# euxoloti_core_rev2.net
KiCad netlist of a schematic drawn in EAGLE
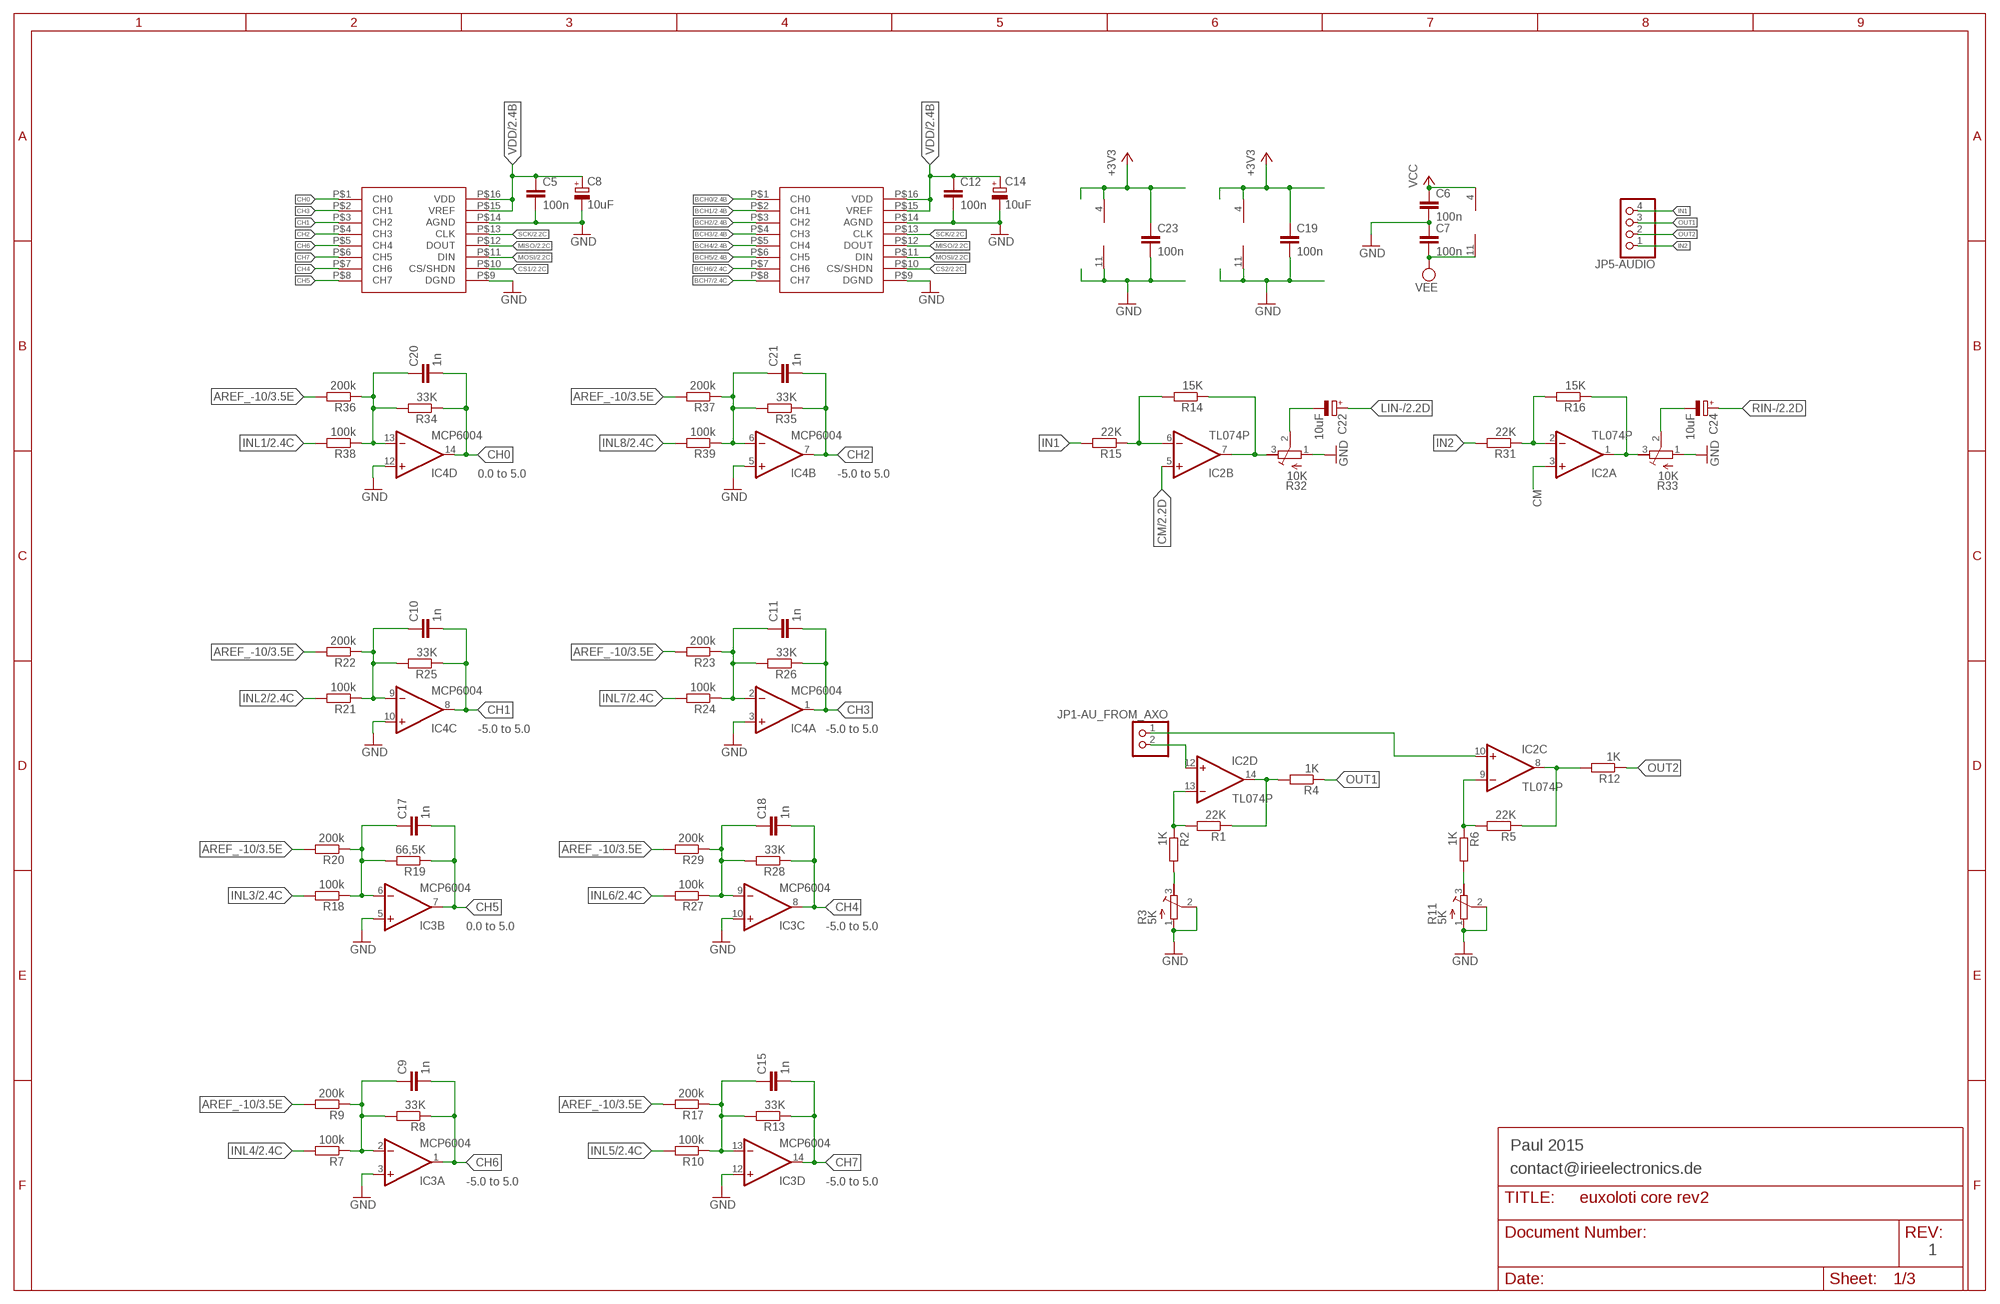
[diagram p0: schematic, sheet 1]
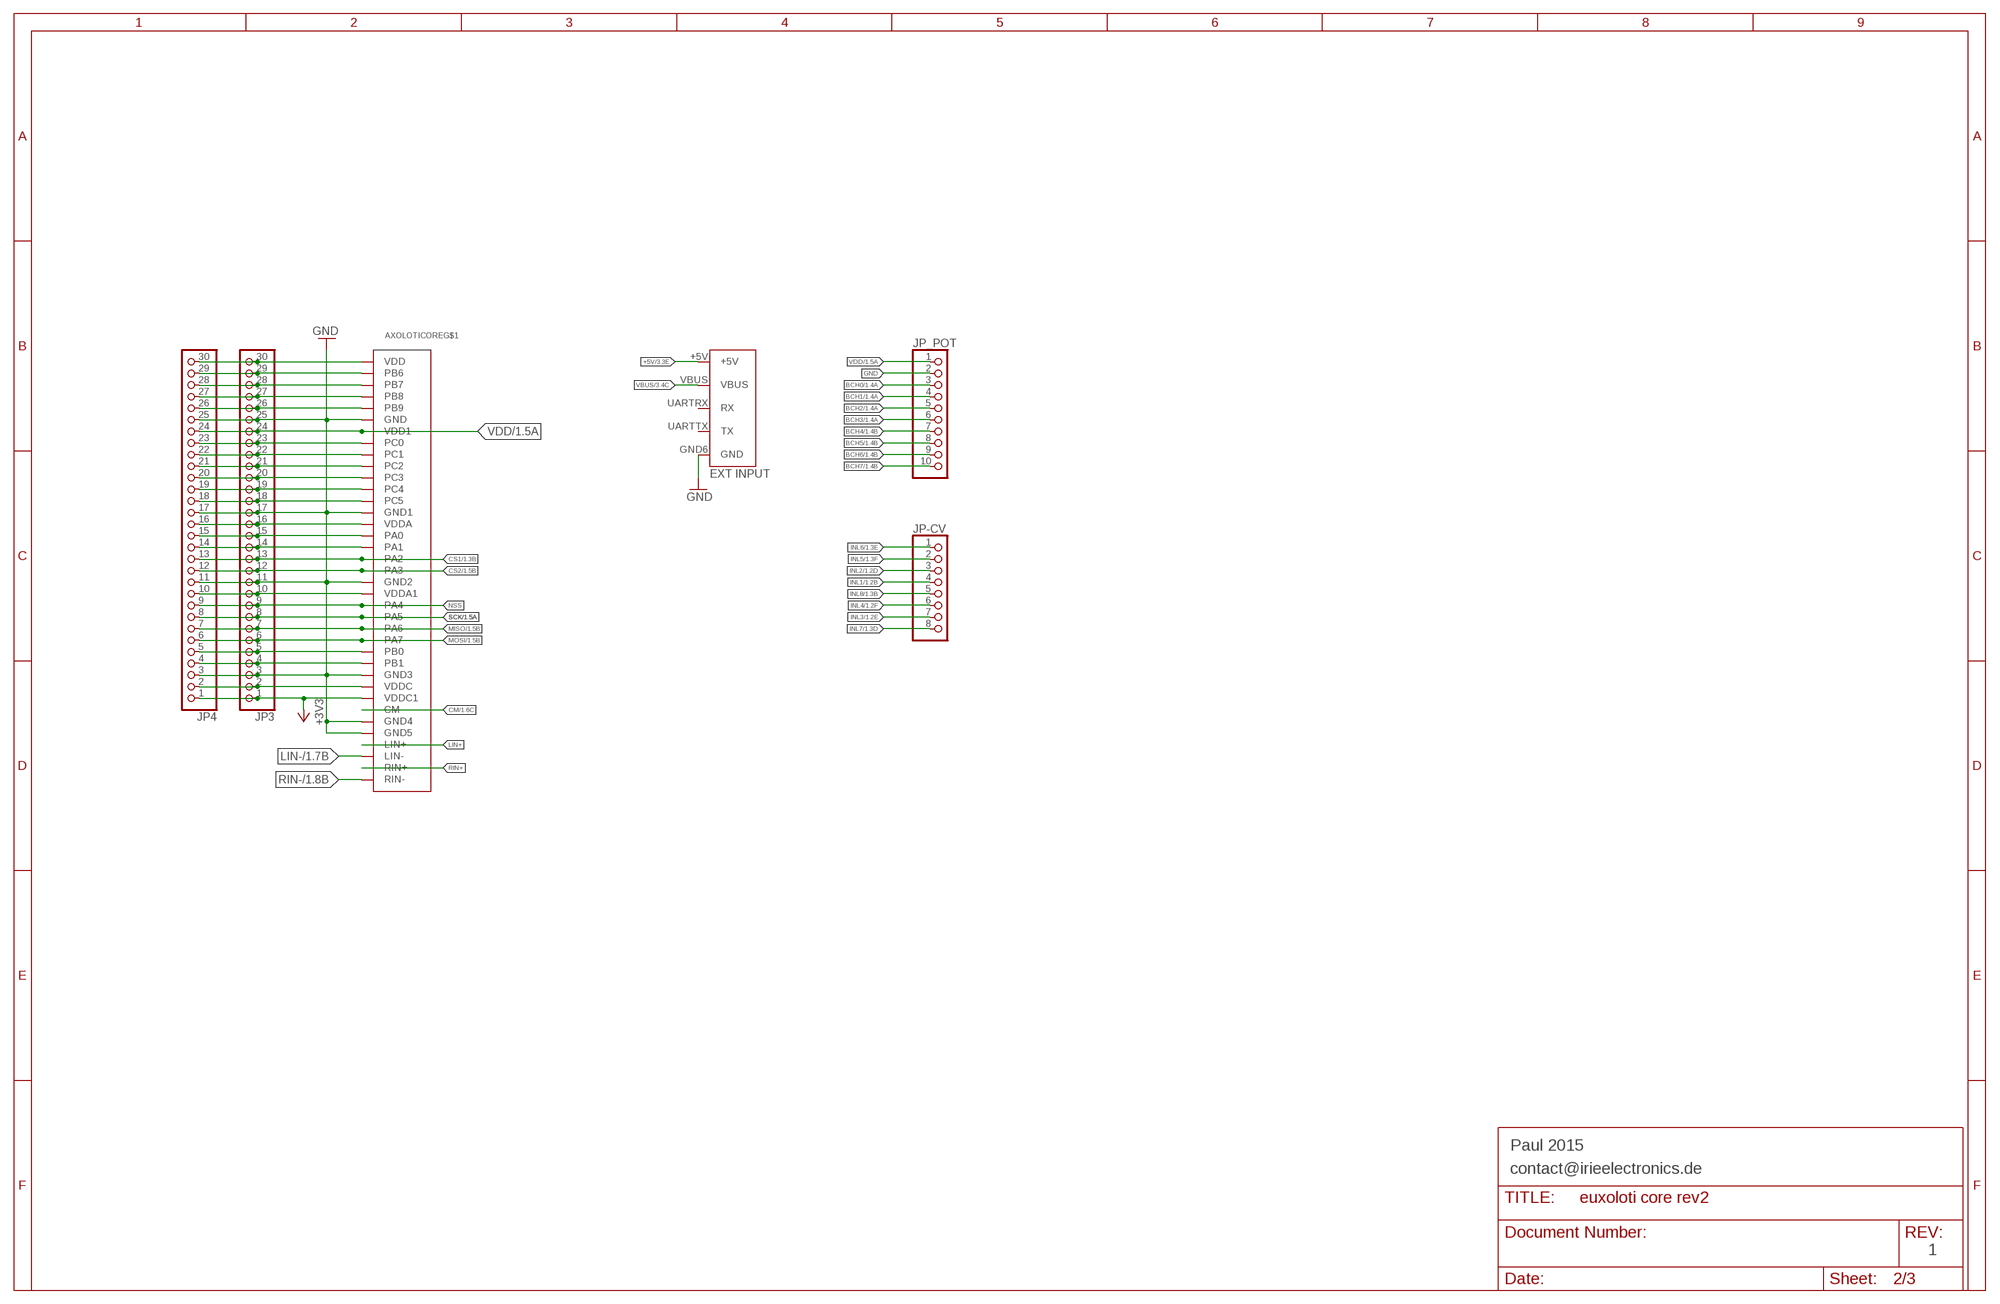
[diagram p1: schematic, sheet 2]
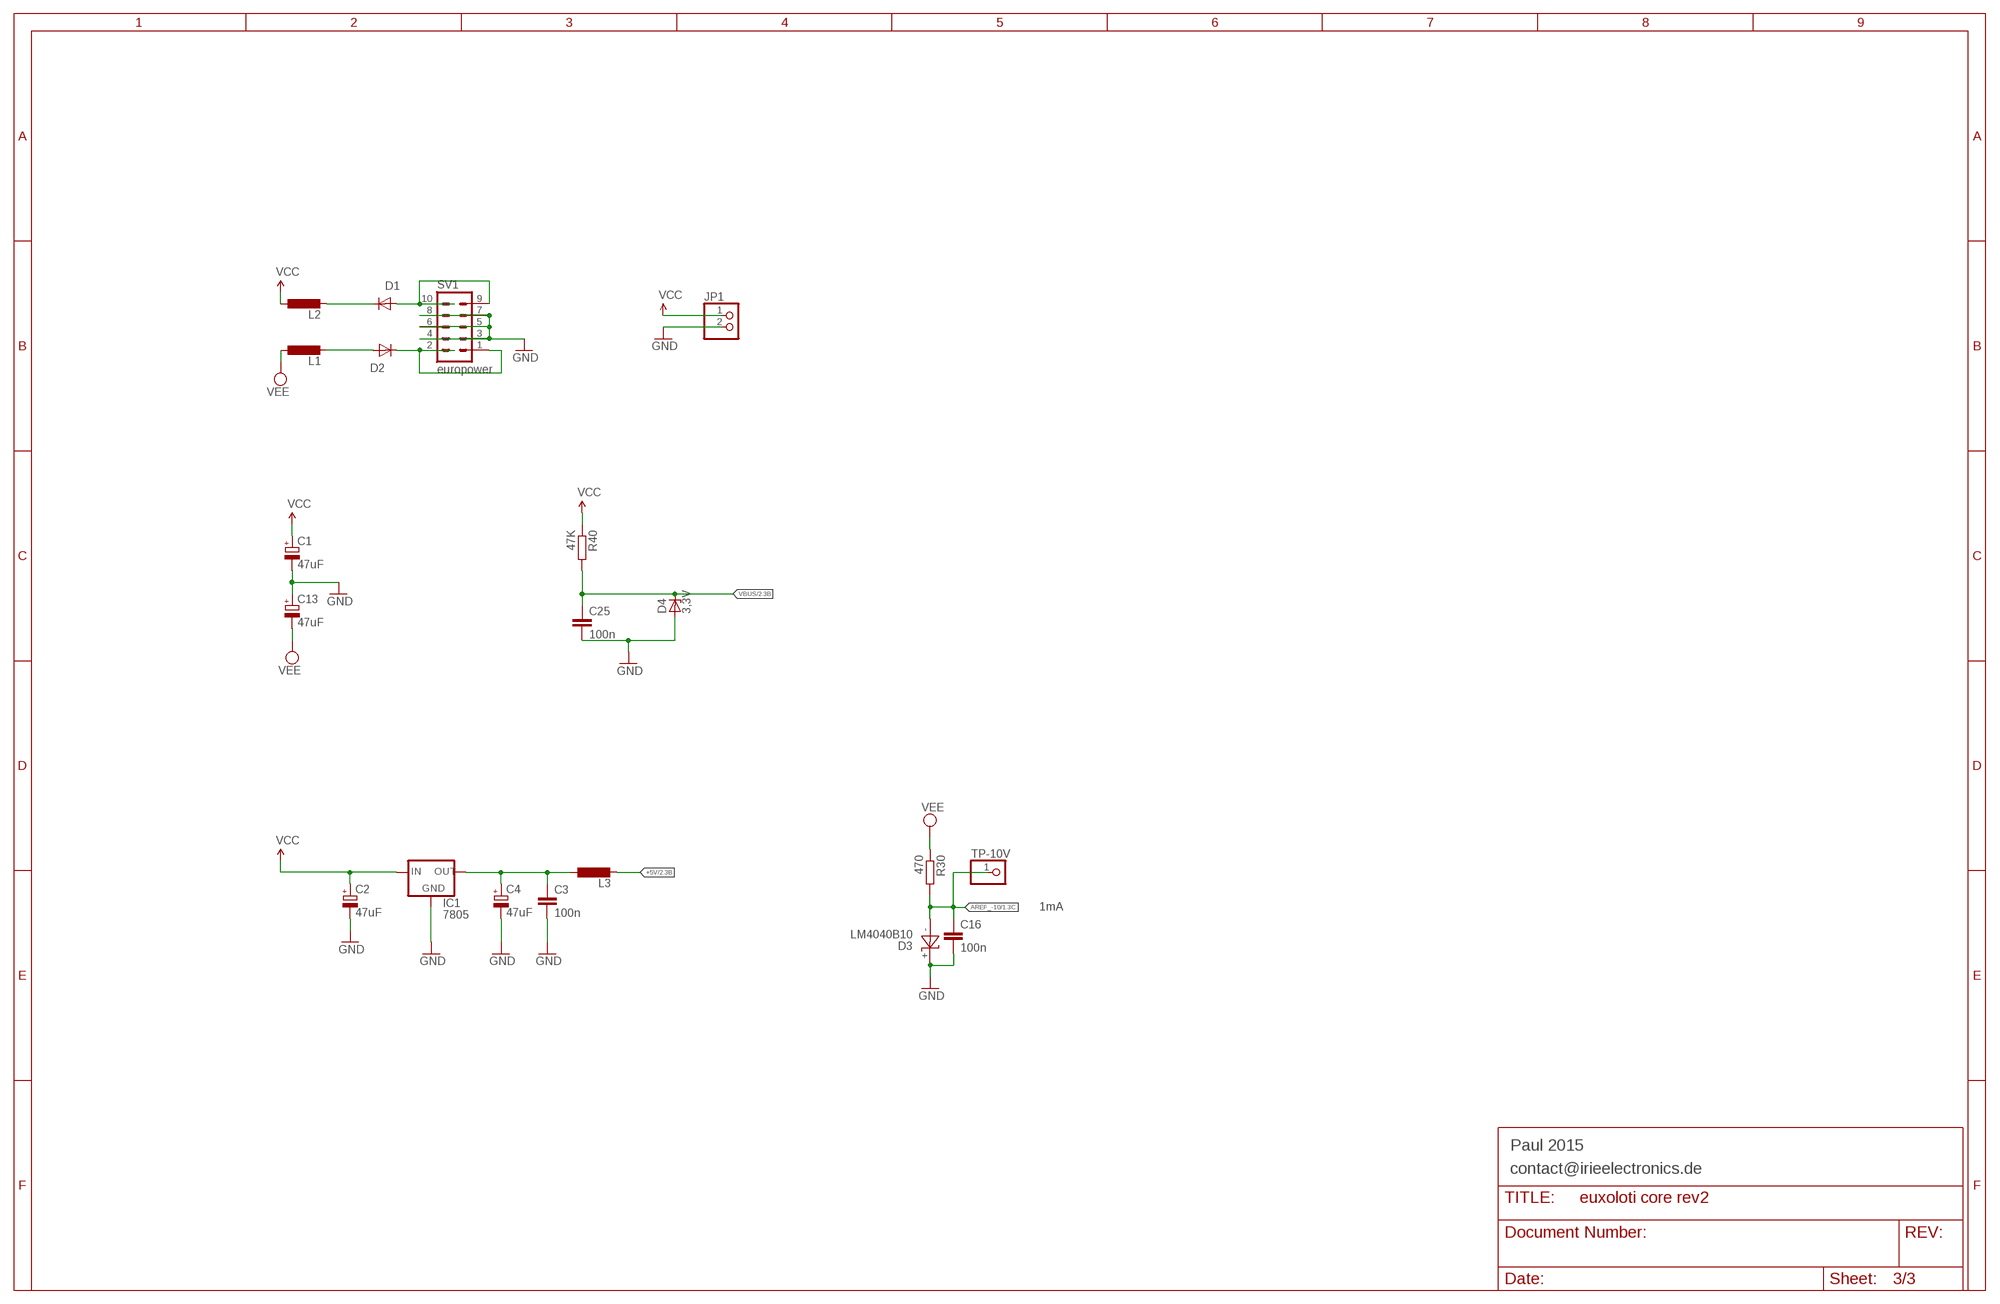
[diagram p2: schematic, sheet 3]

(export (version "E")
  (design (tool "Eeschema 10.0.6"))
  (components
    (comp (ref "C1")
      (value "47uF")
      (footprint "eagle-import:E2-5")
      (libsource (lib "eagle-import") (part "CPOL-EUE2-5"))
    )
    (comp (ref "C2")
      (value "47uF")
      (footprint "eagle-import:E2-5")
      (libsource (lib "eagle-import") (part "CPOL-EUE2-5"))
    )
    (comp (ref "C3")
      (value "100n")
      (footprint "eagle-import:C025-025X050")
      (libsource (lib "eagle-import") (part "C-EU025-025X050"))
    )
    (comp (ref "C4")
      (value "47uF")
      (footprint "eagle-import:E2,5-5")
      (libsource (lib "eagle-import") (part "CPOL-EUE2.5-5"))
    )
    (comp (ref "C13")
      (value "47uF")
      (footprint "eagle-import:E2-5")
      (libsource (lib "eagle-import") (part "CPOL-EUE2-5"))
    )
    (comp (ref "C16")
      (value "100n")
      (footprint "eagle-import:C025-025X050")
      (libsource (lib "eagle-import") (part "C-EU025-025X050"))
    )
    (comp (ref "C25")
      (value "100n")
      (footprint "eagle-import:C025-025X050")
      (libsource (lib "eagle-import") (part "C-EU025-025X050"))
    )
    (comp (ref "D1")
      (value "1N5819HW")
      (footprint "eagle-import:DO35-10")
      (libsource (lib "eagle-import") (part "1N4148DO35-10"))
    )
    (comp (ref "D2")
      (value "1N5819HW")
      (footprint "eagle-import:DO35-10")
      (libsource (lib "eagle-import") (part "1N4148DO35-10"))
    )
    (comp (ref "D3")
      (value "LM4040B10")
      (footprint "eagle-import:TO-92")
      (libsource (lib "eagle-import") (part "LM4040DIP"))
    )
    (comp (ref "D4")
      (value "3,3V")
      (footprint "eagle-import:DO35Z10")
      (libsource (lib "eagle-import") (part "1N821"))
    )
    (comp (ref "IC1")
      (value "7805")
      (footprint "eagle-import:78XXS")
      (libsource (lib "eagle-import") (part "78XXS"))
    )
    (comp (ref "JP1")
      (value "PINHD-1X2")
      (footprint "eagle-import:1X02")
      (libsource (lib "eagle-import") (part "PINHD-1X2"))
    )
    (comp (ref "L1")
      (value "L-EU0207/10")
      (footprint "eagle-import:0207_10")
      (libsource (lib "eagle-import") (part "L-EU0207/10"))
    )
    (comp (ref "L2")
      (value "L-EU0207/10")
      (footprint "eagle-import:0207_10")
      (libsource (lib "eagle-import") (part "L-EU0207/10"))
    )
    (comp (ref "L3")
      (value "L-EU0207/10")
      (footprint "eagle-import:0207_10")
      (libsource (lib "eagle-import") (part "L-EU0207/10"))
    )
    (comp (ref "R30")
      (value "470")
      (footprint "eagle-import:0207_12")
      (libsource (lib "eagle-import") (part "R-EU_0207/12"))
    )
    (comp (ref "R40")
      (value "47K")
      (footprint "eagle-import:0207_7")
      (libsource (lib "eagle-import") (part "R-EU_0207/7"))
    )
    (comp (ref "SV1")
      (value "europower")
      (footprint "eagle-import:EURO_PWR_HEADER_FAT")
      (libsource (lib "eagle-import") (part "EURO_POWER_HEADERFAT_PADS"))
    )
    (comp (ref "TP-10V")
      (value "PINHD-1X1_2.54")
      (footprint "eagle-import:1X01")
      (libsource (lib "eagle-import") (part "PINHD-1X1_2.54"))
    )
    (comp (ref "C5")
      (value "100n")
      (footprint "eagle-import:C025-025X050")
      (libsource (lib "eagle-import") (part "C-EU025-025X050"))
    )
    (comp (ref "C6")
      (value "100n")
      (footprint "eagle-import:C025-025X050")
      (libsource (lib "eagle-import") (part "C-EU025-025X050"))
    )
    (comp (ref "C7")
      (value "100n")
      (footprint "eagle-import:C025-025X050")
      (libsource (lib "eagle-import") (part "C-EU025-025X050"))
    )
    (comp (ref "C8")
      (value "10uF")
      (footprint "eagle-import:E1,8-4")
      (libsource (lib "eagle-import") (part "CPOL-EUE1.8-4"))
    )
    (comp (ref "C9")
      (value "1n")
      (footprint "eagle-import:C050-025X075")
      (libsource (lib "eagle-import") (part "C-EU050-025X075"))
    )
    (comp (ref "C10")
      (value "1n")
      (footprint "eagle-import:C050-025X075")
      (libsource (lib "eagle-import") (part "C-EU050-025X075"))
    )
    (comp (ref "C11")
      (value "1n")
      (footprint "eagle-import:C050-025X075")
      (libsource (lib "eagle-import") (part "C-EU050-025X075"))
    )
    (comp (ref "C12")
      (value "100n")
      (footprint "eagle-import:C025-025X050")
      (libsource (lib "eagle-import") (part "C-EU025-025X050"))
    )
    (comp (ref "C14")
      (value "10uF")
      (footprint "eagle-import:E1,8-4")
      (libsource (lib "eagle-import") (part "CPOL-EUE1.8-4"))
    )
    (comp (ref "C15")
      (value "1n")
      (footprint "eagle-import:C050-025X075")
      (libsource (lib "eagle-import") (part "C-EU050-025X075"))
    )
    (comp (ref "C17")
      (value "1n")
      (footprint "eagle-import:C050-025X075")
      (libsource (lib "eagle-import") (part "C-EU050-025X075"))
    )
    (comp (ref "C18")
      (value "1n")
      (footprint "eagle-import:C050-025X075")
      (libsource (lib "eagle-import") (part "C-EU050-025X075"))
    )
    (comp (ref "C19")
      (value "100n")
      (footprint "eagle-import:C025-025X050")
      (libsource (lib "eagle-import") (part "C-EU025-025X050"))
    )
    (comp (ref "C20")
      (value "1n")
      (footprint "eagle-import:C050-025X075")
      (libsource (lib "eagle-import") (part "C-EU050-025X075"))
    )
    (comp (ref "C21")
      (value "1n")
      (footprint "eagle-import:C050-025X075")
      (libsource (lib "eagle-import") (part "C-EU050-025X075"))
    )
    (comp (ref "C22")
      (value "10uF")
      (footprint "eagle-import:E1,8-4")
      (libsource (lib "eagle-import") (part "CPOL-EUE1.8-4"))
    )
    (comp (ref "C23")
      (value "100n")
      (footprint "eagle-import:C025-025X050")
      (libsource (lib "eagle-import") (part "C-EU025-025X050"))
    )
    (comp (ref "C24")
      (value "10uF")
      (footprint "eagle-import:E1,8-4")
      (libsource (lib "eagle-import") (part "CPOL-EUE1.8-4"))
    )
    (comp (ref "IC2")
      (value "TL074P")
      (footprint "eagle-import:DIL14")
      (libsource (lib "eagle-import") (part "TL074P"))
    )
    (comp (ref "IC3")
      (value "MCP6004")
      (footprint "eagle-import:DIL14")
      (libsource (lib "eagle-import") (part "TL074P"))
    )
    (comp (ref "IC4")
      (value "MCP6004")
      (footprint "eagle-import:DIL14")
      (libsource (lib "eagle-import") (part "TL074P"))
    )
    (comp (ref "JP1-AU_FROM_AXO")
      (value "PINHD-1X2/90")
      (footprint "eagle-import:1X02_90")
      (libsource (lib "eagle-import") (part "PINHD-1X2/90"))
    )
    (comp (ref "JP5-AUDIO")
      (value "PINHD-1X4_2.54")
      (footprint "eagle-import:1X04")
      (libsource (lib "eagle-import") (part "PINHD-1X4_2.54"))
    )
    (comp (ref "R1")
      (value "22K")
      (footprint "eagle-import:0207_10")
      (libsource (lib "eagle-import") (part "R-EU_0207/10"))
    )
    (comp (ref "R2")
      (value "1K")
      (footprint "eagle-import:0207_12")
      (libsource (lib "eagle-import") (part "R-EU_0207/12"))
    )
    (comp (ref "R3")
      (value "5K")
      (footprint "eagle-import:RTRIM3296P")
      (libsource (lib "eagle-import") (part "R-TRIMM3296P"))
    )
    (comp (ref "R4")
      (value "1K")
      (footprint "eagle-import:0207_7")
      (libsource (lib "eagle-import") (part "R-EU_0207/7"))
    )
    (comp (ref "R5")
      (value "22K")
      (footprint "eagle-import:0207_7")
      (libsource (lib "eagle-import") (part "R-EU_0207/7"))
    )
    (comp (ref "R6")
      (value "1K")
      (footprint "eagle-import:0207_7")
      (libsource (lib "eagle-import") (part "R-EU_0207/7"))
    )
    (comp (ref "R7")
      (value "100k")
      (footprint "eagle-import:0207_7")
      (libsource (lib "eagle-import") (part "R-EU_0207/7"))
    )
    (comp (ref "R8")
      (value "33K")
      (footprint "eagle-import:0207_7")
      (libsource (lib "eagle-import") (part "R-EU_0207/7"))
    )
    (comp (ref "R9")
      (value "200k")
      (footprint "eagle-import:0207_10")
      (libsource (lib "eagle-import") (part "R-EU_0207/10"))
    )
    (comp (ref "R10")
      (value "100k")
      (footprint "eagle-import:0207_7")
      (libsource (lib "eagle-import") (part "R-EU_0207/7"))
    )
    (comp (ref "R11")
      (value "5K")
      (footprint "eagle-import:RTRIM3296P")
      (libsource (lib "eagle-import") (part "R-TRIMM3296P"))
    )
    (comp (ref "R12")
      (value "1K")
      (footprint "eagle-import:0207_10")
      (libsource (lib "eagle-import") (part "R-EU_0207/10"))
    )
    (comp (ref "R13")
      (value "33K")
      (footprint "eagle-import:0207_7")
      (libsource (lib "eagle-import") (part "R-EU_0207/7"))
    )
    (comp (ref "R14")
      (value "15K")
      (footprint "eagle-import:0207_7")
      (libsource (lib "eagle-import") (part "R-EU_0207/7"))
    )
    (comp (ref "R15")
      (value "22K")
      (footprint "eagle-import:0207_7")
      (libsource (lib "eagle-import") (part "R-EU_0207/7"))
    )
    (comp (ref "R16")
      (value "15K")
      (footprint "eagle-import:0207_7")
      (libsource (lib "eagle-import") (part "R-EU_0207/7"))
    )
    (comp (ref "R17")
      (value "200k")
      (footprint "eagle-import:0207_7")
      (libsource (lib "eagle-import") (part "R-EU_0207/7"))
    )
    (comp (ref "R18")
      (value "100k")
      (footprint "eagle-import:0207_7")
      (libsource (lib "eagle-import") (part "R-EU_0207/7"))
    )
    (comp (ref "R19")
      (value "66,5K")
      (footprint "eagle-import:0207_7")
      (libsource (lib "eagle-import") (part "R-EU_0207/7"))
    )
    (comp (ref "R20")
      (value "200k")
      (footprint "eagle-import:0207_10")
      (libsource (lib "eagle-import") (part "R-EU_0207/10"))
    )
    (comp (ref "R21")
      (value "100k")
      (footprint "eagle-import:0207_7")
      (libsource (lib "eagle-import") (part "R-EU_0207/7"))
    )
    (comp (ref "R22")
      (value "200k")
      (footprint "eagle-import:0207_7")
      (libsource (lib "eagle-import") (part "R-EU_0207/7"))
    )
    (comp (ref "R23")
      (value "200k")
      (footprint "eagle-import:0207_7")
      (libsource (lib "eagle-import") (part "R-EU_0207/7"))
    )
    (comp (ref "R24")
      (value "100k")
      (footprint "eagle-import:0207_10")
      (libsource (lib "eagle-import") (part "R-EU_0207/10"))
    )
    (comp (ref "R25")
      (value "33K")
      (footprint "eagle-import:0207_7")
      (libsource (lib "eagle-import") (part "R-EU_0207/7"))
    )
    (comp (ref "R26")
      (value "33K")
      (footprint "eagle-import:0207_7")
      (libsource (lib "eagle-import") (part "R-EU_0207/7"))
    )
    (comp (ref "R27")
      (value "100k")
      (footprint "eagle-import:0207_7")
      (libsource (lib "eagle-import") (part "R-EU_0207/7"))
    )
    (comp (ref "R28")
      (value "33K")
      (footprint "eagle-import:0207_7")
      (libsource (lib "eagle-import") (part "R-EU_0207/7"))
    )
    (comp (ref "R29")
      (value "200k")
      (footprint "eagle-import:0207_7")
      (libsource (lib "eagle-import") (part "R-EU_0207/7"))
    )
    (comp (ref "R31")
      (value "22K")
      (footprint "eagle-import:0207_7")
      (libsource (lib "eagle-import") (part "R-EU_0207/7"))
    )
    (comp (ref "R32")
      (value "10K")
      (footprint "eagle-import:RTRIM3296P")
      (libsource (lib "eagle-import") (part "R-TRIMM3296P"))
    )
    (comp (ref "R33")
      (value "10K")
      (footprint "eagle-import:RTRIM3296P")
      (libsource (lib "eagle-import") (part "R-TRIMM3296P"))
    )
    (comp (ref "R34")
      (value "33K")
      (footprint "eagle-import:0207_7")
      (libsource (lib "eagle-import") (part "R-EU_0207/7"))
    )
    (comp (ref "R35")
      (value "33K")
      (footprint "eagle-import:0207_7")
      (libsource (lib "eagle-import") (part "R-EU_0207/7"))
    )
    (comp (ref "R36")
      (value "200k")
      (footprint "eagle-import:0207_7")
      (libsource (lib "eagle-import") (part "R-EU_0207/7"))
    )
    (comp (ref "R37")
      (value "200k")
      (footprint "eagle-import:0207_7")
      (libsource (lib "eagle-import") (part "R-EU_0207/7"))
    )
    (comp (ref "R38")
      (value "100k")
      (footprint "eagle-import:0207_7")
      (libsource (lib "eagle-import") (part "R-EU_0207/7"))
    )
    (comp (ref "R39")
      (value "100k")
      (footprint "eagle-import:0207_7")
      (libsource (lib "eagle-import") (part "R-EU_0207/7"))
    )
    (comp (ref "U$4")
      (value "MCP3208_DIP")
      (footprint "eagle-import:MCP2308")
      (libsource (lib "eagle-import") (part "MCP3208_DIP"))
    )
    (comp (ref "U$5")
      (value "MCP3208_DIP")
      (footprint "eagle-import:MCP2308")
      (libsource (lib "eagle-import") (part "MCP3208_DIP"))
    )
    (comp (ref "AXOLOTICORE")
      (value "AXOLOTI-CORE")
      (footprint "eagle-import:AXOLOTI-CORE")
      (libsource (lib "eagle-import") (part "AXOLOTI-CORE"))
    )
    (comp (ref "JP-CV")
      (value "PINHD-1X8_2.54")
      (footprint "eagle-import:1X08")
      (libsource (lib "eagle-import") (part "PINHD-1X8_2.54"))
    )
    (comp (ref "JP3")
      (value "PINHD-1X30")
      (footprint "eagle-import:1X30")
      (libsource (lib "eagle-import") (part "PINHD-1X30"))
    )
    (comp (ref "JP4")
      (value "PINHD-1X30")
      (footprint "eagle-import:1X30")
      (libsource (lib "eagle-import") (part "PINHD-1X30"))
    )
    (comp (ref "JP_POT")
      (value "PINHD-1X10")
      (footprint "eagle-import:1X10")
      (libsource (lib "eagle-import") (part "PINHD-1X10"))
    )
  )
  (nets
    (net (code "1") (name "+3V3") (class "Default")
      (node (ref "AXOLOTICORE") (pin "VDDC1") (pinfunction "VDDC1_VDDC1") (pintype "bidirectional"))
      (node (ref "C19") (pin "1") (pinfunction "1_1") (pintype "passive"))
      (node (ref "C23") (pin "1") (pinfunction "1_1") (pintype "passive"))
      (node (ref "IC3") (pin "4") (pinfunction "V+_4") (pintype "power_in"))
      (node (ref "IC4") (pin "4") (pinfunction "V+_4") (pintype "power_in"))
      (node (ref "JP3") (pin "1") (pinfunction "1_1") (pintype "passive"))
      (node (ref "JP4") (pin "1") (pinfunction "1_1") (pintype "passive"))
    )
    (net (code "2") (name "+5V") (class "Default")
      (node (ref "AXOLOTICORE") (pin "+5V") (pinfunction "+5V_+5V") (pintype "bidirectional"))
      (node (ref "L3") (pin "2") (pinfunction "2_2") (pintype "passive"))
    )
    (net (code "3") (name "AREF_-10") (class "Default")
      (node (ref "C16") (pin "1") (pinfunction "1_1") (pintype "passive"))
      (node (ref "D3") (pin "-") (pinfunction "-_-") (pintype "output"))
      (node (ref "R17") (pin "2") (pinfunction "2_2") (pintype "passive"))
      (node (ref "R20") (pin "2") (pinfunction "2_2") (pintype "passive"))
      (node (ref "R22") (pin "2") (pinfunction "2_2") (pintype "passive"))
      (node (ref "R23") (pin "2") (pinfunction "2_2") (pintype "passive"))
      (node (ref "R29") (pin "2") (pinfunction "2_2") (pintype "passive"))
      (node (ref "R30") (pin "2") (pinfunction "2_2") (pintype "passive"))
      (node (ref "R36") (pin "2") (pinfunction "2_2") (pintype "passive"))
      (node (ref "R37") (pin "2") (pinfunction "2_2") (pintype "passive"))
      (node (ref "R9") (pin "2") (pinfunction "2_2") (pintype "passive"))
      (node (ref "TP-10V") (pin "1") (pinfunction "1_1") (pintype "passive"))
    )
    (net (code "4") (name "BCH0") (class "Default")
      (node (ref "JP_POT") (pin "3") (pinfunction "3_3") (pintype "passive"))
      (node (ref "U$5") (pin "P$1") (pinfunction "CH0_P$1") (pintype "bidirectional"))
    )
    (net (code "5") (name "BCH1") (class "Default")
      (node (ref "JP_POT") (pin "4") (pinfunction "4_4") (pintype "passive"))
      (node (ref "U$5") (pin "P$2") (pinfunction "CH1_P$2") (pintype "bidirectional"))
    )
    (net (code "6") (name "BCH2") (class "Default")
      (node (ref "JP_POT") (pin "5") (pinfunction "5_5") (pintype "passive"))
      (node (ref "U$5") (pin "P$3") (pinfunction "CH2_P$3") (pintype "bidirectional"))
    )
    (net (code "7") (name "BCH3") (class "Default")
      (node (ref "JP_POT") (pin "6") (pinfunction "6_6") (pintype "passive"))
      (node (ref "U$5") (pin "P$4") (pinfunction "CH3_P$4") (pintype "bidirectional"))
    )
    (net (code "8") (name "BCH4") (class "Default")
      (node (ref "JP_POT") (pin "7") (pinfunction "7_7") (pintype "passive"))
      (node (ref "U$5") (pin "P$5") (pinfunction "CH4_P$5") (pintype "bidirectional"))
    )
    (net (code "9") (name "BCH5") (class "Default")
      (node (ref "JP_POT") (pin "8") (pinfunction "8_8") (pintype "passive"))
      (node (ref "U$5") (pin "P$6") (pinfunction "CH5_P$6") (pintype "bidirectional"))
    )
    (net (code "10") (name "BCH6") (class "Default")
      (node (ref "JP_POT") (pin "9") (pinfunction "9_9") (pintype "passive"))
      (node (ref "U$5") (pin "P$7") (pinfunction "CH6_P$7") (pintype "bidirectional"))
    )
    (net (code "11") (name "BCH7") (class "Default")
      (node (ref "JP_POT") (pin "10") (pinfunction "10_10") (pintype "passive"))
      (node (ref "U$5") (pin "P$8") (pinfunction "CH7_P$8") (pintype "bidirectional"))
    )
    (net (code "12") (name "CH0") (class "Default")
      (node (ref "C20") (pin "2") (pinfunction "2_2") (pintype "passive"))
      (node (ref "IC4") (pin "14") (pinfunction "OUT_14") (pintype "output"))
      (node (ref "R34") (pin "1") (pinfunction "1_1") (pintype "passive"))
      (node (ref "U$4") (pin "P$1") (pinfunction "CH0_P$1") (pintype "bidirectional"))
    )
    (net (code "13") (name "CH1") (class "Default")
      (node (ref "C10") (pin "2") (pinfunction "2_2") (pintype "passive"))
      (node (ref "IC4") (pin "8") (pinfunction "OUT_8") (pintype "output"))
      (node (ref "R25") (pin "1") (pinfunction "1_1") (pintype "passive"))
      (node (ref "U$4") (pin "P$3") (pinfunction "CH2_P$3") (pintype "bidirectional"))
    )
    (net (code "14") (name "CH2") (class "Default")
      (node (ref "C21") (pin "2") (pinfunction "2_2") (pintype "passive"))
      (node (ref "IC4") (pin "7") (pinfunction "OUT_7") (pintype "output"))
      (node (ref "R35") (pin "1") (pinfunction "1_1") (pintype "passive"))
      (node (ref "U$4") (pin "P$4") (pinfunction "CH3_P$4") (pintype "bidirectional"))
    )
    (net (code "15") (name "CH3") (class "Default")
      (node (ref "C11") (pin "2") (pinfunction "2_2") (pintype "passive"))
      (node (ref "IC4") (pin "1") (pinfunction "OUT_1") (pintype "output"))
      (node (ref "R26") (pin "1") (pinfunction "1_1") (pintype "passive"))
      (node (ref "U$4") (pin "P$2") (pinfunction "CH1_P$2") (pintype "bidirectional"))
    )
    (net (code "16") (name "CH4") (class "Default")
      (node (ref "C18") (pin "2") (pinfunction "2_2") (pintype "passive"))
      (node (ref "IC3") (pin "8") (pinfunction "OUT_8") (pintype "output"))
      (node (ref "R28") (pin "1") (pinfunction "1_1") (pintype "passive"))
      (node (ref "U$4") (pin "P$7") (pinfunction "CH6_P$7") (pintype "bidirectional"))
    )
    (net (code "17") (name "CH5") (class "Default")
      (node (ref "C17") (pin "2") (pinfunction "2_2") (pintype "passive"))
      (node (ref "IC3") (pin "7") (pinfunction "OUT_7") (pintype "output"))
      (node (ref "R19") (pin "1") (pinfunction "1_1") (pintype "passive"))
      (node (ref "U$4") (pin "P$8") (pinfunction "CH7_P$8") (pintype "bidirectional"))
    )
    (net (code "18") (name "CH6") (class "Default")
      (node (ref "C9") (pin "2") (pinfunction "2_2") (pintype "passive"))
      (node (ref "IC3") (pin "1") (pinfunction "OUT_1") (pintype "output"))
      (node (ref "R8") (pin "1") (pinfunction "1_1") (pintype "passive"))
      (node (ref "U$4") (pin "P$5") (pinfunction "CH4_P$5") (pintype "bidirectional"))
    )
    (net (code "19") (name "CH7") (class "Default")
      (node (ref "C15") (pin "2") (pinfunction "2_2") (pintype "passive"))
      (node (ref "IC3") (pin "14") (pinfunction "OUT_14") (pintype "output"))
      (node (ref "R13") (pin "1") (pinfunction "1_1") (pintype "passive"))
      (node (ref "U$4") (pin "P$6") (pinfunction "CH5_P$6") (pintype "bidirectional"))
    )
    (net (code "20") (name "CM") (class "Default")
      (node (ref "AXOLOTICORE") (pin "CM") (pinfunction "CM_CM") (pintype "bidirectional"))
      (node (ref "IC2") (pin "3") (pinfunction "+IN_3") (pintype "input"))
      (node (ref "IC2") (pin "5") (pinfunction "+IN_5") (pintype "input"))
    )
    (net (code "21") (name "CS1") (class "Default")
      (node (ref "AXOLOTICORE") (pin "PA2") (pinfunction "PA2_PA2") (pintype "bidirectional"))
      (node (ref "JP3") (pin "13") (pinfunction "13_13") (pintype "passive"))
      (node (ref "JP4") (pin "13") (pinfunction "13_13") (pintype "passive"))
      (node (ref "U$4") (pin "P$10") (pinfunction "CS/SHDN_P$10") (pintype "bidirectional"))
    )
    (net (code "22") (name "CS2") (class "Default")
      (node (ref "AXOLOTICORE") (pin "PA3") (pinfunction "PA3_PA3") (pintype "bidirectional"))
      (node (ref "JP3") (pin "12") (pinfunction "12_12") (pintype "passive"))
      (node (ref "JP4") (pin "12") (pinfunction "12_12") (pintype "passive"))
      (node (ref "U$5") (pin "P$10") (pinfunction "CS/SHDN_P$10") (pintype "bidirectional"))
    )
    (net (code "23") (name "GND") (class "Default")
      (node (ref "AXOLOTICORE") (pin "GND") (pinfunction "GND_GND") (pintype "bidirectional"))
      (node (ref "AXOLOTICORE") (pin "GND1") (pinfunction "GND1_GND1") (pintype "bidirectional"))
      (node (ref "AXOLOTICORE") (pin "GND2") (pinfunction "GND3_GND2") (pintype "bidirectional"))
      (node (ref "AXOLOTICORE") (pin "GND3") (pinfunction "GND2_GND3") (pintype "bidirectional"))
      (node (ref "AXOLOTICORE") (pin "GND4") (pinfunction "GND4_GND4") (pintype "bidirectional"))
      (node (ref "AXOLOTICORE") (pin "GND5") (pinfunction "GND5_GND5") (pintype "bidirectional"))
      (node (ref "AXOLOTICORE") (pin "GND6") (pinfunction "GND_GND6") (pintype "bidirectional"))
      (node (ref "C1") (pin "-") (pinfunction "-_-") (pintype "passive"))
      (node (ref "C12") (pin "2") (pinfunction "2_2") (pintype "passive"))
      (node (ref "C13") (pin "+") (pinfunction "+_+") (pintype "passive"))
      (node (ref "C14") (pin "-") (pinfunction "-_-") (pintype "passive"))
      (node (ref "C16") (pin "2") (pinfunction "2_2") (pintype "passive"))
      (node (ref "C19") (pin "2") (pinfunction "2_2") (pintype "passive"))
      (node (ref "C2") (pin "-") (pinfunction "-_-") (pintype "passive"))
      (node (ref "C23") (pin "2") (pinfunction "2_2") (pintype "passive"))
      (node (ref "C25") (pin "2") (pinfunction "2_2") (pintype "passive"))
      (node (ref "C3") (pin "2") (pinfunction "2_2") (pintype "passive"))
      (node (ref "C4") (pin "-") (pinfunction "-_-") (pintype "passive"))
      (node (ref "C5") (pin "2") (pinfunction "2_2") (pintype "passive"))
      (node (ref "C6") (pin "2") (pinfunction "2_2") (pintype "passive"))
      (node (ref "C7") (pin "1") (pinfunction "1_1") (pintype "passive"))
      (node (ref "C8") (pin "-") (pinfunction "-_-") (pintype "passive"))
      (node (ref "D3") (pin "+") (pinfunction "+_+") (pintype "input"))
      (node (ref "D4") (pin "A") (pinfunction "A_A") (pintype "passive"))
      (node (ref "IC1") (pin "GND") (pinfunction "GND_GND") (pintype "input"))
      (node (ref "IC3") (pin "10") (pinfunction "+IN_10") (pintype "input"))
      (node (ref "IC3") (pin "11") (pinfunction "V-_11") (pintype "power_in"))
      (node (ref "IC3") (pin "12") (pinfunction "+IN_12") (pintype "input"))
      (node (ref "IC3") (pin "3") (pinfunction "+IN_3") (pintype "input"))
      (node (ref "IC3") (pin "5") (pinfunction "+IN_5") (pintype "input"))
      (node (ref "IC4") (pin "10") (pinfunction "+IN_10") (pintype "input"))
      (node (ref "IC4") (pin "11") (pinfunction "V-_11") (pintype "power_in"))
      (node (ref "IC4") (pin "12") (pinfunction "+IN_12") (pintype "input"))
      (node (ref "IC4") (pin "3") (pinfunction "+IN_3") (pintype "input"))
      (node (ref "IC4") (pin "5") (pinfunction "+IN_5") (pintype "input"))
      (node (ref "JP1") (pin "2") (pinfunction "2_2") (pintype "passive"))
      (node (ref "JP3") (pin "11") (pinfunction "11_11") (pintype "passive"))
      (node (ref "JP3") (pin "17") (pinfunction "17_17") (pintype "passive"))
      (node (ref "JP3") (pin "25") (pinfunction "25_25") (pintype "passive"))
      (node (ref "JP3") (pin "3") (pinfunction "3_3") (pintype "passive"))
      (node (ref "JP4") (pin "11") (pinfunction "11_11") (pintype "passive"))
      (node (ref "JP4") (pin "17") (pinfunction "17_17") (pintype "passive"))
      (node (ref "JP4") (pin "25") (pinfunction "25_25") (pintype "passive"))
      (node (ref "JP4") (pin "3") (pinfunction "3_3") (pintype "passive"))
      (node (ref "JP_POT") (pin "2") (pinfunction "2_2") (pintype "passive"))
      (node (ref "R11") (pin "1") (pinfunction "E_1") (pintype "passive"))
      (node (ref "R11") (pin "2") (pinfunction "S_2") (pintype "passive"))
      (node (ref "R3") (pin "1") (pinfunction "E_1") (pintype "passive"))
      (node (ref "R3") (pin "2") (pinfunction "S_2") (pintype "passive"))
      (node (ref "R32") (pin "1") (pinfunction "E_1") (pintype "passive"))
      (node (ref "R33") (pin "1") (pinfunction "E_1") (pintype "passive"))
      (node (ref "SV1") (pin "3") (pinfunction "3_3") (pintype "passive"))
      (node (ref "SV1") (pin "4") (pinfunction "4_4") (pintype "passive"))
      (node (ref "SV1") (pin "5") (pinfunction "5_5") (pintype "passive"))
      (node (ref "SV1") (pin "6") (pinfunction "6_6") (pintype "passive"))
      (node (ref "SV1") (pin "7") (pinfunction "7_7") (pintype "passive"))
      (node (ref "SV1") (pin "8") (pinfunction "8_8") (pintype "passive"))
      (node (ref "U$4") (pin "P$14") (pinfunction "AGND_P$14") (pintype "bidirectional"))
      (node (ref "U$4") (pin "P$9") (pinfunction "DGND_P$9") (pintype "bidirectional"))
      (node (ref "U$5") (pin "P$14") (pinfunction "AGND_P$14") (pintype "bidirectional"))
      (node (ref "U$5") (pin "P$9") (pinfunction "DGND_P$9") (pintype "bidirectional"))
    )
    (net (code "24") (name "IN1") (class "Default")
      (node (ref "JP5-AUDIO") (pin "4") (pinfunction "4_4") (pintype "passive"))
      (node (ref "R15") (pin "2") (pinfunction "2_2") (pintype "passive"))
    )
    (net (code "25") (name "IN2") (class "Default")
      (node (ref "JP5-AUDIO") (pin "1") (pinfunction "1_1") (pintype "passive"))
      (node (ref "R31") (pin "2") (pinfunction "2_2") (pintype "passive"))
    )
    (net (code "26") (name "INL1") (class "Default")
      (node (ref "JP-CV") (pin "4") (pinfunction "4_4") (pintype "passive"))
      (node (ref "R38") (pin "2") (pinfunction "2_2") (pintype "passive"))
    )
    (net (code "27") (name "INL2") (class "Default")
      (node (ref "JP-CV") (pin "3") (pinfunction "3_3") (pintype "passive"))
      (node (ref "R21") (pin "2") (pinfunction "2_2") (pintype "passive"))
    )
    (net (code "28") (name "INL3") (class "Default")
      (node (ref "JP-CV") (pin "7") (pinfunction "7_7") (pintype "passive"))
      (node (ref "R18") (pin "2") (pinfunction "2_2") (pintype "passive"))
    )
    (net (code "29") (name "INL4") (class "Default")
      (node (ref "JP-CV") (pin "6") (pinfunction "6_6") (pintype "passive"))
      (node (ref "R7") (pin "2") (pinfunction "2_2") (pintype "passive"))
    )
    (net (code "30") (name "INL5") (class "Default")
      (node (ref "JP-CV") (pin "2") (pinfunction "2_2") (pintype "passive"))
      (node (ref "R10") (pin "2") (pinfunction "2_2") (pintype "passive"))
    )
    (net (code "31") (name "INL6") (class "Default")
      (node (ref "JP-CV") (pin "1") (pinfunction "1_1") (pintype "passive"))
      (node (ref "R27") (pin "2") (pinfunction "2_2") (pintype "passive"))
    )
    (net (code "32") (name "INL7") (class "Default")
      (node (ref "JP-CV") (pin "8") (pinfunction "8_8") (pintype "passive"))
      (node (ref "R24") (pin "2") (pinfunction "2_2") (pintype "passive"))
    )
    (net (code "33") (name "INL8") (class "Default")
      (node (ref "JP-CV") (pin "5") (pinfunction "5_5") (pintype "passive"))
      (node (ref "R39") (pin "2") (pinfunction "2_2") (pintype "passive"))
    )
    (net (code "34") (name "LIN+") (class "Default")
      (node (ref "AXOLOTICORE") (pin "LIN+") (pinfunction "LIN+_LIN+") (pintype "bidirectional"))
    )
    (net (code "35") (name "LIN-") (class "Default")
      (node (ref "AXOLOTICORE") (pin "LIN-") (pinfunction "LIN-_LIN-") (pintype "bidirectional"))
      (node (ref "C22") (pin "+") (pinfunction "+_+") (pintype "passive"))
    )
    (net (code "36") (name "MISO") (class "Default")
      (node (ref "AXOLOTICORE") (pin "PA6") (pinfunction "PA6_PA6") (pintype "bidirectional"))
      (node (ref "JP3") (pin "7") (pinfunction "7_7") (pintype "passive"))
      (node (ref "JP4") (pin "7") (pinfunction "7_7") (pintype "passive"))
      (node (ref "U$4") (pin "P$12") (pinfunction "DOUT_P$12") (pintype "bidirectional"))
      (node (ref "U$5") (pin "P$12") (pinfunction "DOUT_P$12") (pintype "bidirectional"))
    )
    (net (code "37") (name "MOSI") (class "Default")
      (node (ref "AXOLOTICORE") (pin "PA7") (pinfunction "PA7_PA7") (pintype "bidirectional"))
      (node (ref "JP3") (pin "6") (pinfunction "6_6") (pintype "passive"))
      (node (ref "JP4") (pin "6") (pinfunction "6_6") (pintype "passive"))
      (node (ref "U$4") (pin "P$11") (pinfunction "DIN_P$11") (pintype "bidirectional"))
      (node (ref "U$5") (pin "P$11") (pinfunction "DIN_P$11") (pintype "bidirectional"))
    )
    (net (code "38") (name "NSS") (class "Default")
      (node (ref "AXOLOTICORE") (pin "PA4") (pinfunction "PA4_PA4") (pintype "bidirectional"))
      (node (ref "JP3") (pin "9") (pinfunction "9_9") (pintype "passive"))
      (node (ref "JP4") (pin "9") (pinfunction "9_9") (pintype "passive"))
    )
    (net (code "39") (name "Net-(AXOLOTICORE-PadPA0)") (class "Default")
      (node (ref "AXOLOTICORE") (pin "PA0") (pinfunction "PA0_PA0") (pintype "bidirectional"))
      (node (ref "JP3") (pin "15") (pinfunction "15_15") (pintype "passive"))
      (node (ref "JP4") (pin "15") (pinfunction "15_15") (pintype "passive"))
    )
    (net (code "40") (name "Net-(AXOLOTICORE-PadPA1)") (class "Default")
      (node (ref "AXOLOTICORE") (pin "PA1") (pinfunction "PA1_PA1") (pintype "bidirectional"))
      (node (ref "JP3") (pin "14") (pinfunction "14_14") (pintype "passive"))
      (node (ref "JP4") (pin "14") (pinfunction "14_14") (pintype "passive"))
    )
    (net (code "41") (name "Net-(AXOLOTICORE-PadPB0)") (class "Default")
      (node (ref "AXOLOTICORE") (pin "PB0") (pinfunction "PB0_PB0") (pintype "bidirectional"))
      (node (ref "JP3") (pin "5") (pinfunction "5_5") (pintype "passive"))
      (node (ref "JP4") (pin "5") (pinfunction "5_5") (pintype "passive"))
    )
    (net (code "42") (name "Net-(AXOLOTICORE-PadPB1)") (class "Default")
      (node (ref "AXOLOTICORE") (pin "PB1") (pinfunction "PB1_PB1") (pintype "bidirectional"))
      (node (ref "JP3") (pin "4") (pinfunction "4_4") (pintype "passive"))
      (node (ref "JP4") (pin "4") (pinfunction "4_4") (pintype "passive"))
    )
    (net (code "43") (name "Net-(AXOLOTICORE-PadPB6)") (class "Default")
      (node (ref "AXOLOTICORE") (pin "PB6") (pinfunction "PB6_PB6") (pintype "bidirectional"))
      (node (ref "JP3") (pin "29") (pinfunction "29_29") (pintype "passive"))
      (node (ref "JP4") (pin "29") (pinfunction "29_29") (pintype "passive"))
    )
    (net (code "44") (name "Net-(AXOLOTICORE-PadPB7)") (class "Default")
      (node (ref "AXOLOTICORE") (pin "PB7") (pinfunction "PB7_PB7") (pintype "bidirectional"))
      (node (ref "JP3") (pin "28") (pinfunction "28_28") (pintype "passive"))
      (node (ref "JP4") (pin "28") (pinfunction "28_28") (pintype "passive"))
    )
    (net (code "45") (name "Net-(AXOLOTICORE-PadPB8)") (class "Default")
      (node (ref "AXOLOTICORE") (pin "PB8") (pinfunction "PB8_PB8") (pintype "bidirectional"))
      (node (ref "JP3") (pin "27") (pinfunction "27_27") (pintype "passive"))
      (node (ref "JP4") (pin "27") (pinfunction "27_27") (pintype "passive"))
    )
    (net (code "46") (name "Net-(AXOLOTICORE-PadPB9)") (class "Default")
      (node (ref "AXOLOTICORE") (pin "PB9") (pinfunction "PB9_PB9") (pintype "bidirectional"))
      (node (ref "JP3") (pin "26") (pinfunction "26_26") (pintype "passive"))
      (node (ref "JP4") (pin "26") (pinfunction "26_26") (pintype "passive"))
    )
    (net (code "47") (name "Net-(AXOLOTICORE-PadPC0)") (class "Default")
      (node (ref "AXOLOTICORE") (pin "PC0") (pinfunction "PC0_PC0") (pintype "bidirectional"))
      (node (ref "JP3") (pin "23") (pinfunction "23_23") (pintype "passive"))
      (node (ref "JP4") (pin "23") (pinfunction "23_23") (pintype "passive"))
    )
    (net (code "48") (name "Net-(AXOLOTICORE-PadPC1)") (class "Default")
      (node (ref "AXOLOTICORE") (pin "PC1") (pinfunction "PC1_PC1") (pintype "bidirectional"))
      (node (ref "JP3") (pin "22") (pinfunction "22_22") (pintype "passive"))
      (node (ref "JP4") (pin "22") (pinfunction "22_22") (pintype "passive"))
    )
    (net (code "49") (name "Net-(AXOLOTICORE-PadPC2)") (class "Default")
      (node (ref "AXOLOTICORE") (pin "PC2") (pinfunction "PC2_PC2") (pintype "bidirectional"))
      (node (ref "JP3") (pin "21") (pinfunction "21_21") (pintype "passive"))
      (node (ref "JP4") (pin "21") (pinfunction "21_21") (pintype "passive"))
    )
    (net (code "50") (name "Net-(AXOLOTICORE-PadPC3)") (class "Default")
      (node (ref "AXOLOTICORE") (pin "PC3") (pinfunction "PC3_PC3") (pintype "bidirectional"))
      (node (ref "JP3") (pin "20") (pinfunction "20_20") (pintype "passive"))
      (node (ref "JP4") (pin "20") (pinfunction "20_20") (pintype "passive"))
    )
    (net (code "51") (name "Net-(AXOLOTICORE-PadPC4)") (class "Default")
      (node (ref "AXOLOTICORE") (pin "PC4") (pinfunction "PC4_PC4") (pintype "bidirectional"))
      (node (ref "JP3") (pin "19") (pinfunction "19_19") (pintype "passive"))
      (node (ref "JP4") (pin "19") (pinfunction "19_19") (pintype "passive"))
    )
    (net (code "52") (name "Net-(AXOLOTICORE-PadPC5)") (class "Default")
      (node (ref "AXOLOTICORE") (pin "PC5") (pinfunction "PC5_PC5") (pintype "bidirectional"))
      (node (ref "JP3") (pin "18") (pinfunction "18_18") (pintype "passive"))
      (node (ref "JP4") (pin "18") (pinfunction "18_18") (pintype "passive"))
    )
    (net (code "53") (name "Net-(AXOLOTICORE-PadVDD)") (class "Default")
      (node (ref "AXOLOTICORE") (pin "VDD") (pinfunction "VDD_VDD") (pintype "bidirectional"))
      (node (ref "JP3") (pin "30") (pinfunction "30_30") (pintype "passive"))
      (node (ref "JP4") (pin "30") (pinfunction "30_30") (pintype "passive"))
    )
    (net (code "54") (name "Net-(AXOLOTICORE-PadVDDA)") (class "Default")
      (node (ref "AXOLOTICORE") (pin "VDDA") (pinfunction "VDDA_VDDA") (pintype "bidirectional"))
      (node (ref "JP3") (pin "16") (pinfunction "16_16") (pintype "passive"))
      (node (ref "JP4") (pin "16") (pinfunction "16_16") (pintype "passive"))
    )
    (net (code "55") (name "Net-(AXOLOTICORE-PadVDDA1)") (class "Default")
      (node (ref "AXOLOTICORE") (pin "VDDA1") (pinfunction "VDDA1_VDDA1") (pintype "bidirectional"))
      (node (ref "JP3") (pin "10") (pinfunction "10_10") (pintype "passive"))
      (node (ref "JP4") (pin "10") (pinfunction "10_10") (pintype "passive"))
    )
    (net (code "56") (name "Net-(AXOLOTICORE-PadVDDC)") (class "Default")
      (node (ref "AXOLOTICORE") (pin "VDDC") (pinfunction "VDDC_VDDC") (pintype "bidirectional"))
      (node (ref "JP3") (pin "2") (pinfunction "2_2") (pintype "passive"))
      (node (ref "JP4") (pin "2") (pinfunction "2_2") (pintype "passive"))
    )
    (net (code "57") (name "Net-(C3-Pad1)") (class "Default")
      (node (ref "C3") (pin "1") (pinfunction "1_1") (pintype "passive"))
      (node (ref "C4") (pin "+") (pinfunction "+_+") (pintype "passive"))
      (node (ref "IC1") (pin "OUT") (pinfunction "OUT_OUT") (pintype "passive"))
      (node (ref "L3") (pin "1") (pinfunction "1_1") (pintype "passive"))
    )
    (net (code "58") (name "Net-(D1-PadA)") (class "Default")
      (node (ref "D1") (pin "A") (pinfunction "A_A") (pintype "passive"))
      (node (ref "SV1") (pin "10") (pinfunction "10_10") (pintype "passive"))
      (node (ref "SV1") (pin "9") (pinfunction "9_9") (pintype "passive"))
    )
    (net (code "59") (name "Net-(D1-PadC)") (class "Default")
      (node (ref "D1") (pin "C") (pinfunction "C_C") (pintype "passive"))
      (node (ref "L2") (pin "2") (pinfunction "2_2") (pintype "passive"))
    )
    (net (code "60") (name "Net-(D2-PadA)") (class "Default")
      (node (ref "D2") (pin "A") (pinfunction "A_A") (pintype "passive"))
      (node (ref "L1") (pin "2") (pinfunction "2_2") (pintype "passive"))
    )
    (net (code "61") (name "Net-(D2-PadC)") (class "Default")
      (node (ref "D2") (pin "C") (pinfunction "C_C") (pintype "passive"))
      (node (ref "SV1") (pin "1") (pinfunction "1_1") (pintype "passive"))
      (node (ref "SV1") (pin "2") (pinfunction "2_2") (pintype "passive"))
    )
    (net (code "62") (name "Net-(IC2A--IN)") (class "Default")
      (node (ref "IC2") (pin "2") (pinfunction "-IN_2") (pintype "input"))
      (node (ref "R16") (pin "2") (pinfunction "2_2") (pintype "passive"))
      (node (ref "R31") (pin "1") (pinfunction "1_1") (pintype "passive"))
    )
    (net (code "63") (name "Net-(IC2A-OUT)") (class "Default")
      (node (ref "IC2") (pin "1") (pinfunction "OUT_1") (pintype "output"))
      (node (ref "R16") (pin "1") (pinfunction "1_1") (pintype "passive"))
      (node (ref "R33") (pin "3") (pinfunction "A_3") (pintype "passive"))
    )
    (net (code "64") (name "Net-(IC2B--IN)") (class "Default")
      (node (ref "IC2") (pin "6") (pinfunction "-IN_6") (pintype "input"))
      (node (ref "R14") (pin "2") (pinfunction "2_2") (pintype "passive"))
      (node (ref "R15") (pin "1") (pinfunction "1_1") (pintype "passive"))
    )
    (net (code "65") (name "Net-(IC2B-OUT)") (class "Default")
      (node (ref "IC2") (pin "7") (pinfunction "OUT_7") (pintype "output"))
      (node (ref "R14") (pin "1") (pinfunction "1_1") (pintype "passive"))
      (node (ref "R32") (pin "3") (pinfunction "A_3") (pintype "passive"))
    )
    (net (code "66") (name "Net-(IC2C-+IN)") (class "Default")
      (node (ref "IC2") (pin "10") (pinfunction "+IN_10") (pintype "input"))
      (node (ref "JP1-AU_FROM_AXO") (pin "1") (pinfunction "1_1") (pintype "passive"))
    )
    (net (code "67") (name "Net-(IC2C--IN)") (class "Default")
      (node (ref "IC2") (pin "9") (pinfunction "-IN_9") (pintype "input"))
      (node (ref "R5") (pin "2") (pinfunction "2_2") (pintype "passive"))
      (node (ref "R6") (pin "1") (pinfunction "1_1") (pintype "passive"))
    )
    (net (code "68") (name "Net-(IC2C-OUT)") (class "Default")
      (node (ref "IC2") (pin "8") (pinfunction "OUT_8") (pintype "output"))
      (node (ref "R12") (pin "2") (pinfunction "2_2") (pintype "passive"))
      (node (ref "R5") (pin "1") (pinfunction "1_1") (pintype "passive"))
    )
    (net (code "69") (name "Net-(IC2D-+IN)") (class "Default")
      (node (ref "IC2") (pin "12") (pinfunction "+IN_12") (pintype "input"))
      (node (ref "JP1-AU_FROM_AXO") (pin "2") (pinfunction "2_2") (pintype "passive"))
    )
    (net (code "70") (name "Net-(IC2D--IN)") (class "Default")
      (node (ref "IC2") (pin "13") (pinfunction "-IN_13") (pintype "input"))
      (node (ref "R1") (pin "2") (pinfunction "2_2") (pintype "passive"))
      (node (ref "R2") (pin "1") (pinfunction "1_1") (pintype "passive"))
    )
    (net (code "71") (name "Net-(IC2D-OUT)") (class "Default")
      (node (ref "IC2") (pin "14") (pinfunction "OUT_14") (pintype "output"))
      (node (ref "R1") (pin "1") (pinfunction "1_1") (pintype "passive"))
      (node (ref "R4") (pin "2") (pinfunction "2_2") (pintype "passive"))
    )
    (net (code "72") (name "Net-(IC3A--IN)") (class "Default")
      (node (ref "C9") (pin "1") (pinfunction "1_1") (pintype "passive"))
      (node (ref "IC3") (pin "2") (pinfunction "-IN_2") (pintype "input"))
      (node (ref "R7") (pin "1") (pinfunction "1_1") (pintype "passive"))
      (node (ref "R8") (pin "2") (pinfunction "2_2") (pintype "passive"))
      (node (ref "R9") (pin "1") (pinfunction "1_1") (pintype "passive"))
    )
    (net (code "73") (name "Net-(IC3B--IN)") (class "Default")
      (node (ref "C17") (pin "1") (pinfunction "1_1") (pintype "passive"))
      (node (ref "IC3") (pin "6") (pinfunction "-IN_6") (pintype "input"))
      (node (ref "R18") (pin "1") (pinfunction "1_1") (pintype "passive"))
      (node (ref "R19") (pin "2") (pinfunction "2_2") (pintype "passive"))
      (node (ref "R20") (pin "1") (pinfunction "1_1") (pintype "passive"))
    )
    (net (code "74") (name "Net-(IC3C--IN)") (class "Default")
      (node (ref "C18") (pin "1") (pinfunction "1_1") (pintype "passive"))
      (node (ref "IC3") (pin "9") (pinfunction "-IN_9") (pintype "input"))
      (node (ref "R27") (pin "1") (pinfunction "1_1") (pintype "passive"))
      (node (ref "R28") (pin "2") (pinfunction "2_2") (pintype "passive"))
      (node (ref "R29") (pin "1") (pinfunction "1_1") (pintype "passive"))
    )
    (net (code "75") (name "Net-(IC3D--IN)") (class "Default")
      (node (ref "C15") (pin "1") (pinfunction "1_1") (pintype "passive"))
      (node (ref "IC3") (pin "13") (pinfunction "-IN_13") (pintype "input"))
      (node (ref "R10") (pin "1") (pinfunction "1_1") (pintype "passive"))
      (node (ref "R13") (pin "2") (pinfunction "2_2") (pintype "passive"))
      (node (ref "R17") (pin "1") (pinfunction "1_1") (pintype "passive"))
    )
    (net (code "76") (name "Net-(IC4A--IN)") (class "Default")
      (node (ref "C11") (pin "1") (pinfunction "1_1") (pintype "passive"))
      (node (ref "IC4") (pin "2") (pinfunction "-IN_2") (pintype "input"))
      (node (ref "R23") (pin "1") (pinfunction "1_1") (pintype "passive"))
      (node (ref "R24") (pin "1") (pinfunction "1_1") (pintype "passive"))
      (node (ref "R26") (pin "2") (pinfunction "2_2") (pintype "passive"))
    )
    (net (code "77") (name "Net-(IC4B--IN)") (class "Default")
      (node (ref "C21") (pin "1") (pinfunction "1_1") (pintype "passive"))
      (node (ref "IC4") (pin "6") (pinfunction "-IN_6") (pintype "input"))
      (node (ref "R35") (pin "2") (pinfunction "2_2") (pintype "passive"))
      (node (ref "R37") (pin "1") (pinfunction "1_1") (pintype "passive"))
      (node (ref "R39") (pin "1") (pinfunction "1_1") (pintype "passive"))
    )
    (net (code "78") (name "Net-(IC4C--IN)") (class "Default")
      (node (ref "C10") (pin "1") (pinfunction "1_1") (pintype "passive"))
      (node (ref "IC4") (pin "9") (pinfunction "-IN_9") (pintype "input"))
      (node (ref "R21") (pin "1") (pinfunction "1_1") (pintype "passive"))
      (node (ref "R22") (pin "1") (pinfunction "1_1") (pintype "passive"))
      (node (ref "R25") (pin "2") (pinfunction "2_2") (pintype "passive"))
    )
    (net (code "79") (name "Net-(IC4D--IN)") (class "Default")
      (node (ref "C20") (pin "1") (pinfunction "1_1") (pintype "passive"))
      (node (ref "IC4") (pin "13") (pinfunction "-IN_13") (pintype "input"))
      (node (ref "R34") (pin "2") (pinfunction "2_2") (pintype "passive"))
      (node (ref "R36") (pin "1") (pinfunction "1_1") (pintype "passive"))
      (node (ref "R38") (pin "1") (pinfunction "1_1") (pintype "passive"))
    )
    (net (code "80") (name "Net-(R3-A)") (class "Default")
      (node (ref "R2") (pin "2") (pinfunction "2_2") (pintype "passive"))
      (node (ref "R3") (pin "3") (pinfunction "A_3") (pintype "passive"))
    )
    (net (code "81") (name "Net-(R11-A)") (class "Default")
      (node (ref "R11") (pin "3") (pinfunction "A_3") (pintype "passive"))
      (node (ref "R6") (pin "2") (pinfunction "2_2") (pintype "passive"))
    )
    (net (code "82") (name "Net-(R32-S)") (class "Default")
      (node (ref "C22") (pin "-") (pinfunction "-_-") (pintype "passive"))
      (node (ref "R32") (pin "2") (pinfunction "S_2") (pintype "passive"))
    )
    (net (code "83") (name "Net-(R33-S)") (class "Default")
      (node (ref "C24") (pin "-") (pinfunction "-_-") (pintype "passive"))
      (node (ref "R33") (pin "2") (pinfunction "S_2") (pintype "passive"))
    )
    (net (code "84") (name "OUT1") (class "Default")
      (node (ref "JP5-AUDIO") (pin "3") (pinfunction "3_3") (pintype "passive"))
      (node (ref "R4") (pin "1") (pinfunction "1_1") (pintype "passive"))
    )
    (net (code "85") (name "OUT2") (class "Default")
      (node (ref "JP5-AUDIO") (pin "2") (pinfunction "2_2") (pintype "passive"))
      (node (ref "R12") (pin "1") (pinfunction "1_1") (pintype "passive"))
    )
    (net (code "86") (name "RIN+") (class "Default")
      (node (ref "AXOLOTICORE") (pin "RIN+") (pinfunction "RIN+_RIN+") (pintype "bidirectional"))
    )
    (net (code "87") (name "RIN-") (class "Default")
      (node (ref "AXOLOTICORE") (pin "RIN-") (pinfunction "RIN-_RIN-") (pintype "bidirectional"))
      (node (ref "C24") (pin "+") (pinfunction "+_+") (pintype "passive"))
    )
    (net (code "88") (name "SCK") (class "Default")
      (node (ref "AXOLOTICORE") (pin "PA5") (pinfunction "PA5_PA5") (pintype "bidirectional"))
      (node (ref "JP3") (pin "8") (pinfunction "8_8") (pintype "passive"))
      (node (ref "JP4") (pin "8") (pinfunction "8_8") (pintype "passive"))
      (node (ref "U$4") (pin "P$13") (pinfunction "CLK_P$13") (pintype "bidirectional"))
      (node (ref "U$5") (pin "P$13") (pinfunction "CLK_P$13") (pintype "bidirectional"))
    )
    (net (code "89") (name "VBUS") (class "Default")
      (node (ref "AXOLOTICORE") (pin "VBUS") (pinfunction "VBUS_VBUS") (pintype "bidirectional"))
      (node (ref "C25") (pin "1") (pinfunction "1_1") (pintype "passive"))
      (node (ref "D4") (pin "C") (pinfunction "C_C") (pintype "passive"))
      (node (ref "R40") (pin "2") (pinfunction "2_2") (pintype "passive"))
    )
    (net (code "90") (name "VCC") (class "Default")
      (node (ref "C1") (pin "+") (pinfunction "+_+") (pintype "passive"))
      (node (ref "C2") (pin "+") (pinfunction "+_+") (pintype "passive"))
      (node (ref "C6") (pin "1") (pinfunction "1_1") (pintype "passive"))
      (node (ref "IC1") (pin "IN") (pinfunction "IN_IN") (pintype "input"))
      (node (ref "IC2") (pin "4") (pinfunction "V+_4") (pintype "power_in"))
      (node (ref "JP1") (pin "1") (pinfunction "1_1") (pintype "passive"))
      (node (ref "L2") (pin "1") (pinfunction "1_1") (pintype "passive"))
      (node (ref "R40") (pin "1") (pinfunction "1_1") (pintype "passive"))
    )
    (net (code "91") (name "VDD") (class "Default")
      (node (ref "AXOLOTICORE") (pin "VDD1") (pinfunction "VDD1_VDD1") (pintype "bidirectional"))
      (node (ref "C12") (pin "1") (pinfunction "1_1") (pintype "passive"))
      (node (ref "C14") (pin "+") (pinfunction "+_+") (pintype "passive"))
      (node (ref "C5") (pin "1") (pinfunction "1_1") (pintype "passive"))
      (node (ref "C8") (pin "+") (pinfunction "+_+") (pintype "passive"))
      (node (ref "JP3") (pin "24") (pinfunction "24_24") (pintype "passive"))
      (node (ref "JP4") (pin "24") (pinfunction "24_24") (pintype "passive"))
      (node (ref "JP_POT") (pin "1") (pinfunction "1_1") (pintype "passive"))
      (node (ref "U$4") (pin "P$15") (pinfunction "VREF_P$15") (pintype "bidirectional"))
      (node (ref "U$4") (pin "P$16") (pinfunction "VDD_P$16") (pintype "bidirectional"))
      (node (ref "U$5") (pin "P$15") (pinfunction "VREF_P$15") (pintype "bidirectional"))
      (node (ref "U$5") (pin "P$16") (pinfunction "VDD_P$16") (pintype "bidirectional"))
    )
    (net (code "92") (name "VEE") (class "Default")
      (node (ref "C13") (pin "-") (pinfunction "-_-") (pintype "passive"))
      (node (ref "C7") (pin "2") (pinfunction "2_2") (pintype "passive"))
      (node (ref "IC2") (pin "11") (pinfunction "V-_11") (pintype "power_in"))
      (node (ref "L1") (pin "1") (pinfunction "1_1") (pintype "passive"))
      (node (ref "R30") (pin "1") (pinfunction "1_1") (pintype "passive"))
    )
    (net (code "93") (name "unconnected-(AXOLOTICOREB-RX-PadUARTRX)") (class "Default")
      (node (ref "AXOLOTICORE") (pin "UARTRX") (pinfunction "RX_UARTRX") (pintype "bidirectional"))
    )
    (net (code "94") (name "unconnected-(AXOLOTICOREB-TX-PadUARTTX)") (class "Default")
      (node (ref "AXOLOTICORE") (pin "UARTTX") (pinfunction "TX_UARTTX") (pintype "bidirectional"))
    )
  )
)
